# qse_blank.net
KiCad netlist of a schematic drawn in Altium Designer
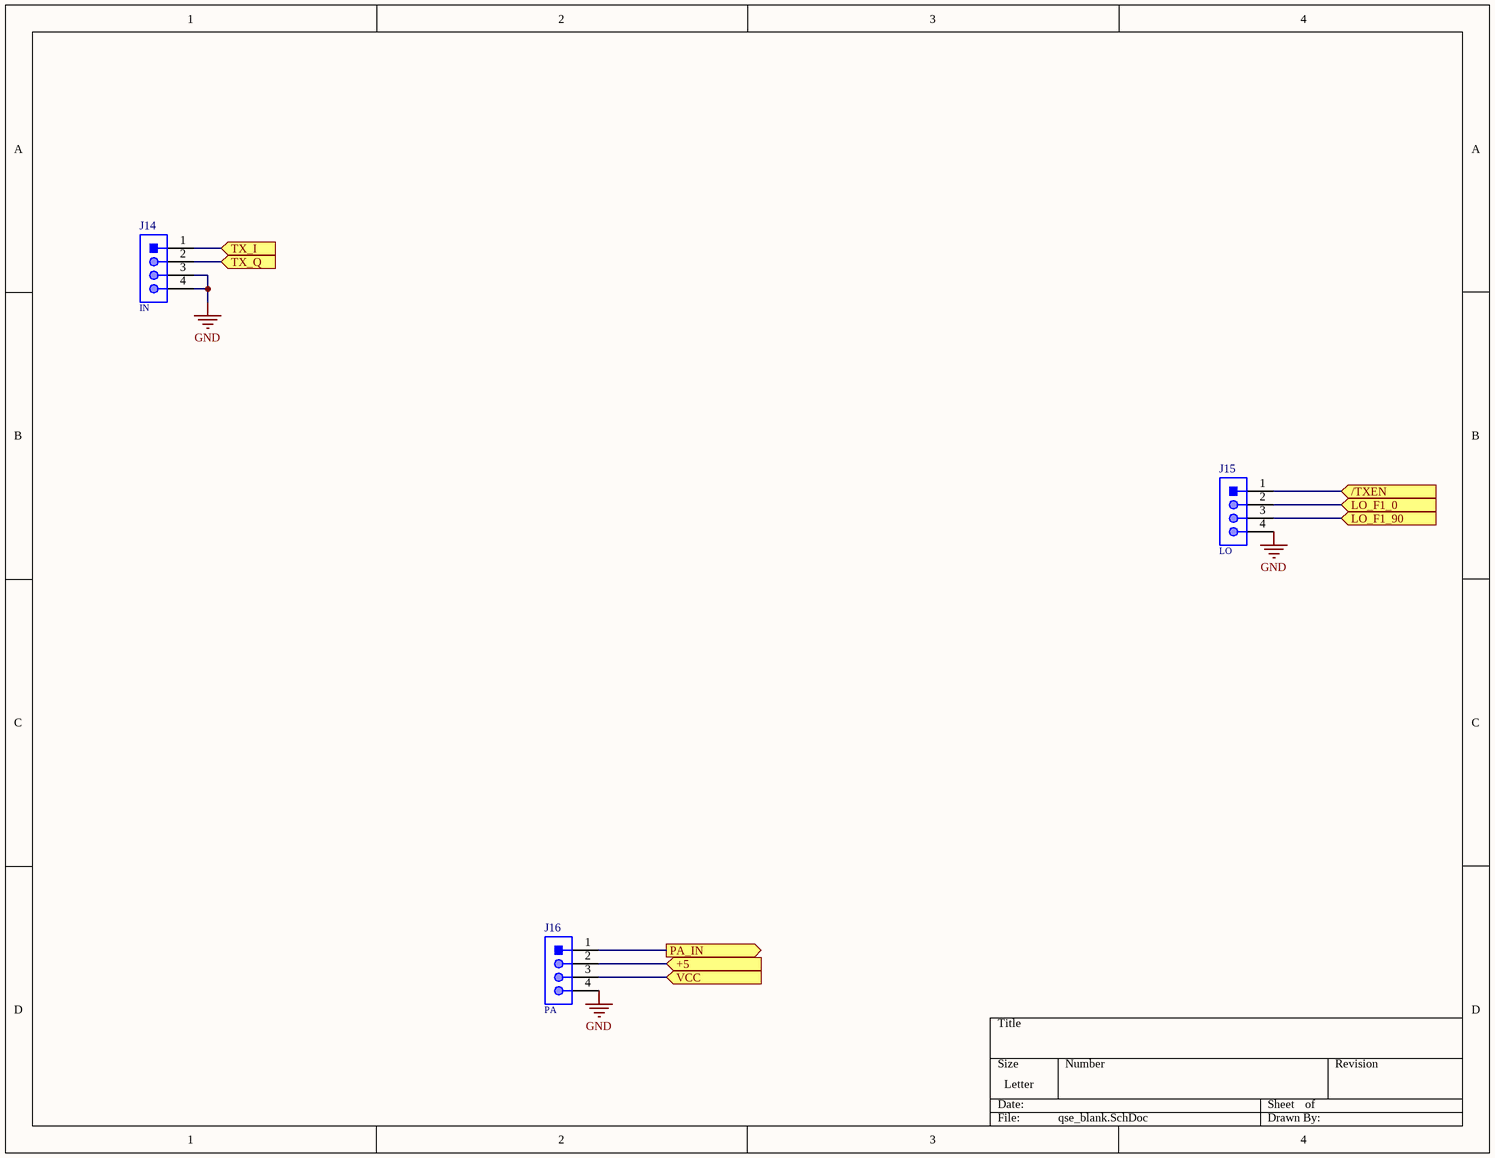
[diagram p0: qse_blank.SchDoc]

(export (version "E")
  (design (tool "Eeschema 10.0.6"))
  (components
    (comp (ref "J14")
      (value "IN")
      (footprint "61300411121")
      (description "THT Vertical Pin Header WR-PHD, Pitch 2.54 mm, Single Row, 4 pins")
      (fields
        (field (name "MANUFACTURER") "Wurth Elektronik")
        (field (name "PART NUMBER") "61300411121")
        (field (name "PUBLISHER") "WurthElektronik")
      )
      (libsource (lib "Altium Content Vault") (part "WE-CN-1P-M-R4"))
    )
    (comp (ref "J15")
      (value "LO")
      (footprint "61300411121")
      (description "THT Vertical Pin Header WR-PHD, Pitch 2.54 mm, Single Row, 4 pins")
      (fields
        (field (name "MANUFACTURER") "Wurth Elektronik")
        (field (name "PART NUMBER") "61300411121")
        (field (name "PUBLISHER") "WurthElektronik")
      )
      (libsource (lib "Altium Content Vault") (part "WE-CN-1P-M-R4"))
    )
    (comp (ref "J16")
      (value "PA")
      (footprint "61300411121")
      (description "THT Vertical Pin Header WR-PHD, Pitch 2.54 mm, Single Row, 4 pins")
      (fields
        (field (name "MANUFACTURER") "Wurth Elektronik")
        (field (name "PART NUMBER") "61300411121")
        (field (name "PUBLISHER") "WurthElektronik")
      )
      (libsource (lib "Altium Content Vault") (part "WE-CN-1P-M-R4"))
    )
  )
  (nets
    (net (code "1") (name "/+5") (class "Default")
      (node (ref "J16") (pin "2") (pinfunction "2_2") (pintype "passive"))
    )
    (net (code "2") (name "/LO_F1_0") (class "Default")
      (node (ref "J15") (pin "2") (pinfunction "2_2") (pintype "passive"))
    )
    (net (code "3") (name "/LO_F1_90") (class "Default")
      (node (ref "J15") (pin "3") (pinfunction "3_3") (pintype "passive"))
    )
    (net (code "4") (name "/PA_IN") (class "Default")
      (node (ref "J16") (pin "1") (pinfunction "1_1") (pintype "passive"))
    )
    (net (code "5") (name "/TX_I") (class "Default")
      (node (ref "J14") (pin "1") (pinfunction "1_1") (pintype "passive"))
    )
    (net (code "6") (name "/TX_Q") (class "Default")
      (node (ref "J14") (pin "2") (pinfunction "2_2") (pintype "passive"))
    )
    (net (code "7") (name "/VCC") (class "Default")
      (node (ref "J16") (pin "3") (pinfunction "3_3") (pintype "passive"))
    )
    (net (code "8") (name "/{slash}TXEN") (class "Default")
      (node (ref "J15") (pin "1") (pinfunction "1_1") (pintype "passive"))
    )
    (net (code "9") (name "GND") (class "Default")
      (node (ref "J14") (pin "3") (pinfunction "3_3") (pintype "passive"))
      (node (ref "J14") (pin "4") (pinfunction "4_4") (pintype "passive"))
      (node (ref "J15") (pin "4") (pinfunction "4_4") (pintype "passive"))
      (node (ref "J16") (pin "4") (pinfunction "4_4") (pintype "passive"))
    )
  )
)
